# cociclo_04.net
KiCad netlist of a schematic drawn in EAGLE
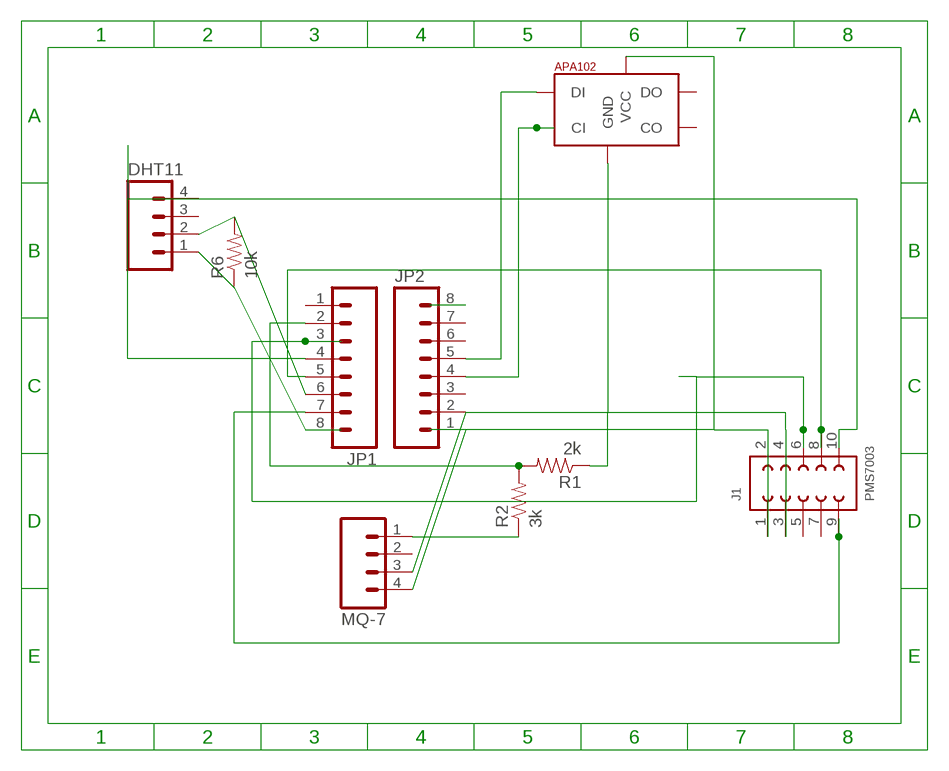
[diagram p0: schematic, sheet 1]

(export (version "E")
  (design (tool "Eeschema 10.0.6"))
  (components
    (comp (ref "DHT11")
      (value "M04PTH")
      (footprint "eagle-import:1X04")
      (libsource (lib "eagle-import") (part "M04PTH"))
    )
    (comp (ref "J1")
      (value "PMS7003")
      (footprint "eagle-import:621X1021021")
      (libsource (lib "eagle-import") (part "621X1021021"))
    )
    (comp (ref "JP1")
      (value "M08")
      (footprint "eagle-import:1X08_ROUND")
      (libsource (lib "eagle-import") (part "M08"))
    )
    (comp (ref "JP2")
      (value "M08")
      (footprint "eagle-import:1X08_ROUND")
      (libsource (lib "eagle-import") (part "M08"))
    )
    (comp (ref "LED")
      (value "APA1025050")
      (footprint "eagle-import:APA102_5050")
      (libsource (lib "eagle-import") (part "APA1025050"))
    )
    (comp (ref "MQ-7")
      (value "M04PTH")
      (footprint "eagle-import:1X04")
      (libsource (lib "eagle-import") (part "M04PTH"))
    )
    (comp (ref "R1")
      (value "2k")
      (footprint "eagle-import:1206")
      (libsource (lib "eagle-import") (part "RESISTOR1206"))
    )
    (comp (ref "R2")
      (value "3k")
      (footprint "eagle-import:1206")
      (libsource (lib "eagle-import") (part "RESISTOR1206"))
    )
    (comp (ref "R6")
      (value "10k")
      (footprint "eagle-import:1206")
      (libsource (lib "eagle-import") (part "RESISTOR1206"))
    )
  )
  (nets
    (net (code "1") (name "Net-(DHT11-Pad1)") (class "Default")
      (node (ref "DHT11") (pin "1") (pinfunction "1_1") (pintype "passive"))
      (node (ref "JP1") (pin "8") (pinfunction "8_8") (pintype "passive"))
      (node (ref "R6") (pin "1") (pinfunction "1_1") (pintype "passive"))
    )
    (net (code "2") (name "Net-(DHT11-Pad2)") (class "Default")
      (node (ref "DHT11") (pin "2") (pinfunction "2_2") (pintype "passive"))
      (node (ref "JP1") (pin "6") (pinfunction "6_6") (pintype "passive"))
      (node (ref "R6") (pin "2") (pinfunction "2_2") (pintype "passive"))
    )
    (net (code "3") (name "Net-(J1-2)") (class "Default")
      (node (ref "DHT11") (pin "4") (pinfunction "4_4") (pintype "passive"))
      (node (ref "J1") (pin "3") (pinfunction "2_3") (pintype "passive"))
      (node (ref "J1") (pin "4") (pinfunction "9_4") (pintype "passive"))
      (node (ref "JP2") (pin "2") (pinfunction "2_2") (pintype "passive"))
      (node (ref "LED") (pin "6") (pinfunction "GND_6") (pintype "bidirectional"))
      (node (ref "MQ-7") (pin "3") (pinfunction "3_3") (pintype "passive"))
      (node (ref "R1") (pin "1") (pinfunction "1_1") (pintype "passive"))
    )
    (net (code "4") (name "Net-(J1-5)") (class "Default")
      (node (ref "J1") (pin "9") (pinfunction "5_9") (pintype "passive"))
      (node (ref "JP1") (pin "7") (pinfunction "7_7") (pintype "passive"))
    )
    (net (code "5") (name "Net-(J1-6)") (class "Default")
      (node (ref "J1") (pin "10") (pinfunction "6_10") (pintype "passive"))
      (node (ref "JP1") (pin "4") (pinfunction "4_4") (pintype "passive"))
    )
    (net (code "6") (name "Net-(J1-7)") (class "Default")
      (node (ref "J1") (pin "8") (pinfunction "7_8") (pintype "passive"))
      (node (ref "JP1") (pin "5") (pinfunction "5_5") (pintype "passive"))
    )
    (net (code "7") (name "Net-(J1-8)") (class "Default")
      (node (ref "J1") (pin "6") (pinfunction "8_6") (pintype "passive"))
      (node (ref "JP1") (pin "3") (pinfunction "3_3") (pintype "passive"))
    )
    (net (code "8") (name "Net-(J1-10)") (class "Default")
      (node (ref "J1") (pin "1") (pinfunction "1_1") (pintype "passive"))
      (node (ref "J1") (pin "2") (pinfunction "10_2") (pintype "passive"))
      (node (ref "JP2") (pin "1") (pinfunction "1_1") (pintype "passive"))
      (node (ref "LED") (pin "1") (pinfunction "VCC_1") (pintype "bidirectional"))
      (node (ref "MQ-7") (pin "4") (pinfunction "4_4") (pintype "passive"))
    )
    (net (code "9") (name "Net-(JP1-Pad2)") (class "Default")
      (node (ref "JP1") (pin "2") (pinfunction "2_2") (pintype "passive"))
      (node (ref "R1") (pin "2") (pinfunction "2_2") (pintype "passive"))
      (node (ref "R2") (pin "2") (pinfunction "2_2") (pintype "passive"))
    )
    (net (code "10") (name "Net-(LED-CI)") (class "Default")
      (node (ref "JP2") (pin "4") (pinfunction "4_4") (pintype "passive"))
      (node (ref "LED") (pin "5") (pinfunction "CI_5") (pintype "bidirectional"))
    )
    (net (code "11") (name "Net-(LED-DI)") (class "Default")
      (node (ref "JP2") (pin "5") (pinfunction "5_5") (pintype "passive"))
      (node (ref "LED") (pin "4") (pinfunction "DI_4") (pintype "bidirectional"))
    )
    (net (code "12") (name "Net-(MQ-7-Pad1)") (class "Default")
      (node (ref "MQ-7") (pin "1") (pinfunction "1_1") (pintype "passive"))
      (node (ref "R2") (pin "1") (pinfunction "1_1") (pintype "passive"))
    )
    (net (code "13") (name "unconnected-(DHT11-Pad3)") (class "Default")
      (node (ref "DHT11") (pin "3") (pinfunction "3_3") (pintype "passive"))
    )
    (net (code "14") (name "unconnected-(J1-3-Pad5)") (class "Default")
      (node (ref "J1") (pin "5") (pinfunction "3_5") (pintype "passive"))
    )
    (net (code "15") (name "unconnected-(J1-4-Pad7)") (class "Default")
      (node (ref "J1") (pin "7") (pinfunction "4_7") (pintype "passive"))
    )
    (net (code "16") (name "unconnected-(JP1-Pad1)") (class "Default")
      (node (ref "JP1") (pin "1") (pinfunction "1_1") (pintype "passive"))
    )
    (net (code "17") (name "unconnected-(JP2-Pad3)") (class "Default")
      (node (ref "JP2") (pin "3") (pinfunction "3_3") (pintype "passive"))
    )
    (net (code "18") (name "unconnected-(JP2-Pad6)") (class "Default")
      (node (ref "JP2") (pin "6") (pinfunction "6_6") (pintype "passive"))
    )
    (net (code "19") (name "unconnected-(JP2-Pad7)") (class "Default")
      (node (ref "JP2") (pin "7") (pinfunction "7_7") (pintype "passive"))
    )
    (net (code "20") (name "unconnected-(JP2-Pad8)") (class "Default")
      (node (ref "JP2") (pin "8") (pinfunction "8_8") (pintype "passive"))
    )
    (net (code "21") (name "unconnected-(LED-CO-Pad2)") (class "Default")
      (node (ref "LED") (pin "2") (pinfunction "CO_2") (pintype "bidirectional"))
    )
    (net (code "22") (name "unconnected-(LED-DO-Pad3)") (class "Default")
      (node (ref "LED") (pin "3") (pinfunction "DO_3") (pintype "bidirectional"))
    )
    (net (code "23") (name "unconnected-(MQ-7-Pad2)") (class "Default")
      (node (ref "MQ-7") (pin "2") (pinfunction "2_2") (pintype "passive"))
    )
  )
)
